# 3_adcs_circuits.net
KiCad netlist of a schematic drawn in Altium Designer
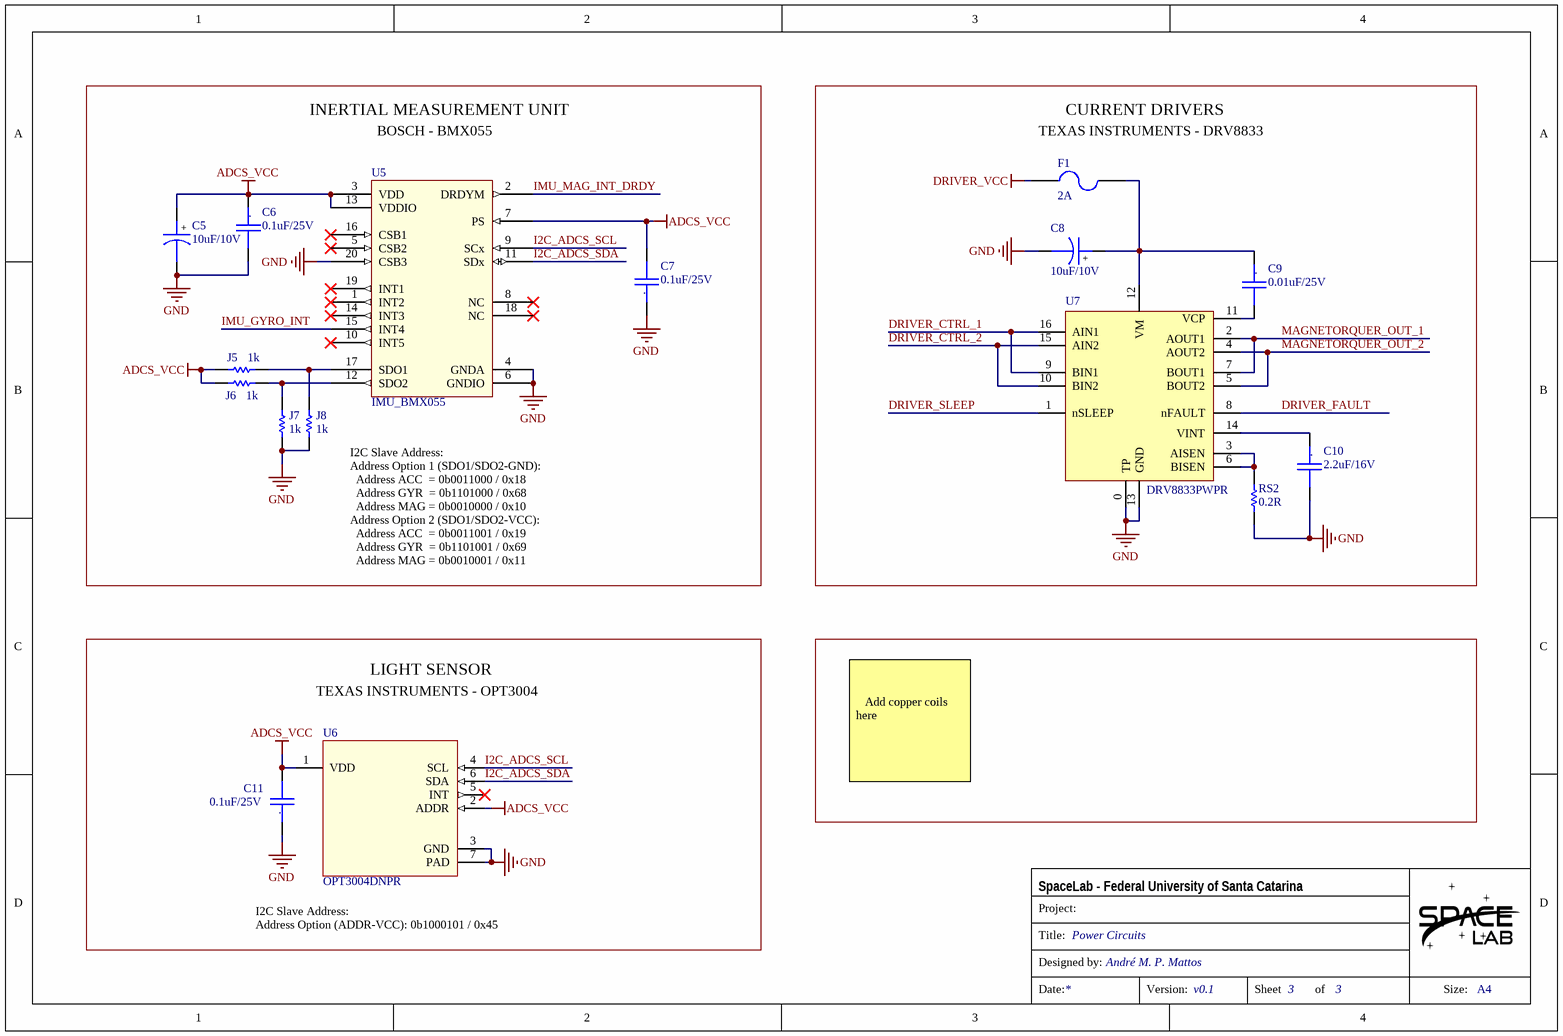
[diagram p0: 3_adcs_circuits.schdoc]

(export (version "E")
  (design (tool "Eeschema 10.0.6"))
  (components
    (comp (ref "C5")
      (value "10uF/10V")
      (footprint "CC0805_Tantalum")
      (description "CAP Tantalum 10uF 10V 20% 0805")
      (fields (field (name "PARTNUMBER") "TPSP106M010R2000"))
      (libsource (lib "schematics_library_legacy") (part "Cap_Tant_SMD_10uF_10V_0805"))
    )
    (comp (ref "C6")
      (value "0.1uF/25V")
      (footprint "CC0805")
      (description "CAP CER 0.1UF 25V 10% X7R 0805")
      (fields (field (name "PARTNUMBER") "CC0805KRX7R8BB104"))
      (libsource (lib "schematics_library_legacy") (part "Cap_Cer_X7R_0.1uF_25V_0805"))
    )
    (comp (ref "C7")
      (value "0.1uF/25V")
      (footprint "CC0805")
      (description "CAP CER 0.1UF 25V 10% X7R 0805")
      (fields (field (name "PARTNUMBER") "CC0805KRX7R8BB104"))
      (libsource (lib "schematics_library_legacy") (part "Cap_Cer_X7R_0.1uF_25V_0805"))
    )
    (comp (ref "C8")
      (value "10uF/10V")
      (footprint "CC0805_Tantalum")
      (description "CAP Tantalum 10uF 10V 20% 0805")
      (fields (field (name "PARTNUMBER") "TPSP106M010R2000"))
      (libsource (lib "schematics_library_legacy") (part "Cap_Tant_SMD_10uF_10V_0805"))
    )
    (comp (ref "C9")
      (value "0.01uF/25V")
      (footprint "CC0805")
      (description "CAP CER 0.01uF 25V 10% X7R 0805")
      (fields (field (name "PARTNUMBER") "CL21B103KAANNNC"))
      (libsource (lib "schematics_library_legacy") (part "Cap_Cer_X7R_0.01uF_50V_0805"))
    )
    (comp (ref "C10")
      (value "2.2uF/16V")
      (footprint "CC0805")
      (description "CAP CER 2.2uF 16V 10% X7R 0805")
      (fields (field (name "PARTNUMBER") "EMF212B7225KGHT"))
      (libsource (lib "schematics_library_legacy") (part "Cap_Cer_X7R_2.2uF_16V_0805"))
    )
    (comp (ref "C11")
      (value "0.1uF/25V")
      (footprint "CC0805")
      (description "CAP CER 0.1UF 25V 10% X7R 0805")
      (fields (field (name "PARTNUMBER") "CC0805KRX7R8BB104"))
      (libsource (lib "schematics_library_legacy") (part "Cap_Cer_X7R_0.1uF_25V_0805"))
    )
    (comp (ref "F1")
      (value "2A")
      (footprint "1206")
      (description "Surface Mount Fuses SMD 1206 Fast Action 2A")
      (fields (field (name "PARTNUMBER") "SF-1206FP200-2"))
      (libsource (lib "schematics_library_legacy") (part "Fuse"))
    )
    (comp (ref "J5")
      (value "1k")
      (footprint "0805")
      (description "RES 1.0K OHM 1/8W 1% 0805")
      (fields (field (name "PARTNUMBER") "RC0805FR-071KL"))
      (libsource (lib "schematics_library_legacy") (part "R1.0k_1%_1/8W_0805"))
    )
    (comp (ref "J6")
      (value "1k")
      (footprint "0805")
      (description "RES 1.0K OHM 1/8W 1% 0805")
      (fields (field (name "PARTNUMBER") "RC0805FR-071KL"))
      (libsource (lib "schematics_library_legacy") (part "R1.0k_1%_1/8W_0805"))
    )
    (comp (ref "J7")
      (value "1k")
      (footprint "0805")
      (description "RES 1.0K OHM 1/8W 1% 0805")
      (fields (field (name "PARTNUMBER") "RC0805FR-071KL"))
      (libsource (lib "schematics_library_legacy") (part "R1.0k_1%_1/8W_0805"))
    )
    (comp (ref "J8")
      (value "1k")
      (footprint "0805")
      (description "RES 1.0K OHM 1/8W 1% 0805")
      (fields (field (name "PARTNUMBER") "RC0805FR-071KL"))
      (libsource (lib "schematics_library_legacy") (part "R1.0k_1%_1/8W_0805"))
    )
    (comp (ref "RS2")
      (value "0.2R")
      (footprint "0805")
      (description "RES 0.2R OHM 1/4W 1% 0805")
      (fields (field (name "PARTNUMBER") "ERJ-U6SFR20V"))
      (libsource (lib "schematics_library_legacy") (part "R0.2_1%_1/4W_0805"))
    )
    (comp (ref "U5")
      (value "IMU_BMX055")
      (footprint "LGA20")
      (libsource (lib "schematics_library_legacy") (part "IMU_BMX055"))
    )
    (comp (ref "U6")
      (value "OPT3004DNPR")
      (footprint "DNP0006A")
      (description "No Description Available")
      (fields
        (field (name "MANUFACTURER") "Texas Instruments")
        (field (name "COPYRIGHT") "Copyright (C) 2018 Accelerated Designs. All rights reserved")
      )
      (libsource (lib "schematics_library_legacy") (part "OPT3004DNPR"))
    )
    (comp (ref "U7")
      (value "DRV8833PWPR")
      (footprint "16TTSSOP")
      (libsource (lib "schematics_library_legacy") (part "DRV8833PWPR"))
    )
  )
  (nets
    (net (code "1") (name "/DRIVER_CTRL_1") (class "Default")
      (node (ref "U7") (pin "16") (pinfunction "AIN1_16") (pintype "passive"))
      (node (ref "U7") (pin "9") (pinfunction "BIN1_9") (pintype "passive"))
    )
    (net (code "2") (name "/DRIVER_CTRL_2") (class "Default")
      (node (ref "U7") (pin "10") (pinfunction "BIN2_10") (pintype "passive"))
      (node (ref "U7") (pin "15") (pinfunction "AIN2_15") (pintype "passive"))
    )
    (net (code "3") (name "/DRIVER_FAULT") (class "Default")
      (node (ref "U7") (pin "8") (pinfunction "nFAULT_8") (pintype "passive"))
    )
    (net (code "4") (name "/DRIVER_SLEEP") (class "Default")
      (node (ref "U7") (pin "1") (pinfunction "nSLEEP_1") (pintype "passive"))
    )
    (net (code "5") (name "/I2C_ADCS_SCL") (class "Default")
      (node (ref "U5") (pin "9") (pinfunction "SCx_9") (pintype "input"))
      (node (ref "U6") (pin "4") (pinfunction "SCL_4") (pintype "input"))
    )
    (net (code "6") (name "/I2C_ADCS_SDA") (class "Default")
      (node (ref "U5") (pin "11") (pinfunction "SDx_11") (pintype "bidirectional"))
      (node (ref "U6") (pin "6") (pinfunction "SDA_6") (pintype "input"))
    )
    (net (code "7") (name "/IMU_GYRO_INT") (class "Default")
      (node (ref "U5") (pin "15") (pinfunction "INT4_15") (pintype "output"))
    )
    (net (code "8") (name "/IMU_MAG_INT_DRDY") (class "Default")
      (node (ref "U5") (pin "2") (pinfunction "DRDYM_2") (pintype "output"))
    )
    (net (code "9") (name "/MAGNETORQUER_OUT_1") (class "Default")
      (node (ref "U7") (pin "2") (pinfunction "AOUT1_2") (pintype "passive"))
      (node (ref "U7") (pin "7") (pinfunction "BOUT1_7") (pintype "passive"))
    )
    (net (code "10") (name "/MAGNETORQUER_OUT_2") (class "Default")
      (node (ref "U7") (pin "4") (pinfunction "AOUT2_4") (pintype "passive"))
      (node (ref "U7") (pin "5") (pinfunction "BOUT2_5") (pintype "passive"))
    )
    (net (code "11") (name "ADCS_VCC") (class "Default")
      (node (ref "C11") (pin "2") (pinfunction "2_2") (pintype "passive"))
      (node (ref "C5") (pin "1") (pinfunction "1_1") (pintype "passive"))
      (node (ref "C6") (pin "1") (pinfunction "1_1") (pintype "passive"))
      (node (ref "C7") (pin "2") (pinfunction "2_2") (pintype "passive"))
      (node (ref "J5") (pin "2") (pinfunction "2_2") (pintype "passive"))
      (node (ref "J6") (pin "2") (pinfunction "2_2") (pintype "passive"))
      (node (ref "U5") (pin "13") (pinfunction "VDDIO_13") (pintype "passive"))
      (node (ref "U5") (pin "3") (pinfunction "VDD_3") (pintype "passive"))
      (node (ref "U5") (pin "7") (pinfunction "PS_7") (pintype "input"))
      (node (ref "U6") (pin "1") (pinfunction "VDD_1") (pintype "power_in"))
      (node (ref "U6") (pin "2") (pinfunction "ADDR_2") (pintype "input"))
    )
    (net (code "12") (name "DRIVER_VCC") (class "Default")
      (node (ref "F1") (pin "2") (pinfunction "2_2") (pintype "passive"))
    )
    (net (code "13") (name "GND") (class "Default")
      (node (ref "C10") (pin "2") (pinfunction "2_2") (pintype "passive"))
      (node (ref "C11") (pin "1") (pinfunction "1_1") (pintype "passive"))
      (node (ref "C5") (pin "2") (pinfunction "2_2") (pintype "passive"))
      (node (ref "C6") (pin "2") (pinfunction "2_2") (pintype "passive"))
      (node (ref "C7") (pin "1") (pinfunction "1_1") (pintype "passive"))
      (node (ref "C8") (pin "2") (pinfunction "2_2") (pintype "passive"))
      (node (ref "J7") (pin "1") (pinfunction "1_1") (pintype "passive"))
      (node (ref "J8") (pin "1") (pinfunction "1_1") (pintype "passive"))
      (node (ref "RS2") (pin "1") (pinfunction "1_1") (pintype "passive"))
      (node (ref "U5") (pin "20") (pinfunction "CSB3_20") (pintype "input"))
      (node (ref "U5") (pin "4") (pinfunction "GNDA_4") (pintype "passive"))
      (node (ref "U5") (pin "6") (pinfunction "GNDIO_6") (pintype "passive"))
      (node (ref "U6") (pin "3") (pinfunction "GND_3") (pintype "power_in"))
      (node (ref "U6") (pin "7") (pinfunction "PAD_7") (pintype "passive"))
      (node (ref "U7") (pin "0") (pinfunction "TP_0") (pintype "passive"))
      (node (ref "U7") (pin "13") (pinfunction "GND_13") (pintype "passive"))
    )
    (net (code "14") (name "Net-(U5-SDO1)") (class "Default")
      (node (ref "J5") (pin "1") (pinfunction "1_1") (pintype "passive"))
      (node (ref "J8") (pin "2") (pinfunction "2_2") (pintype "passive"))
      (node (ref "U5") (pin "17") (pinfunction "SDO1_17") (pintype "passive"))
    )
    (net (code "15") (name "Net-(U5-SDO2)") (class "Default")
      (node (ref "J6") (pin "1") (pinfunction "1_1") (pintype "passive"))
      (node (ref "J7") (pin "2") (pinfunction "2_2") (pintype "passive"))
      (node (ref "U5") (pin "12") (pinfunction "SDO2_12") (pintype "output"))
    )
    (net (code "16") (name "Net-(U7-AISEN)") (class "Default")
      (node (ref "RS2") (pin "2") (pinfunction "2_2") (pintype "passive"))
      (node (ref "U7") (pin "3") (pinfunction "AISEN_3") (pintype "passive"))
      (node (ref "U7") (pin "6") (pinfunction "BISEN_6") (pintype "passive"))
    )
    (net (code "17") (name "Net-(U7-VCP)") (class "Default")
      (node (ref "C9") (pin "2") (pinfunction "2_2") (pintype "passive"))
      (node (ref "U7") (pin "11") (pinfunction "VCP_11") (pintype "passive"))
    )
    (net (code "18") (name "Net-(U7-VINT)") (class "Default")
      (node (ref "C10") (pin "1") (pinfunction "1_1") (pintype "passive"))
      (node (ref "U7") (pin "14") (pinfunction "VINT_14") (pintype "passive"))
    )
    (net (code "19") (name "Net-(U7-VM)") (class "Default")
      (node (ref "C8") (pin "1") (pinfunction "1_1") (pintype "passive"))
      (node (ref "C9") (pin "1") (pinfunction "1_1") (pintype "passive"))
      (node (ref "F1") (pin "1") (pinfunction "1_1") (pintype "passive"))
      (node (ref "U7") (pin "12") (pinfunction "VM_12") (pintype "passive"))
    )
    (net (code "20") (name "unconnected-(U5-CSB1-Pad16)") (class "Default")
      (node (ref "U5") (pin "16") (pinfunction "CSB1_16") (pintype "input+no_connect"))
    )
    (net (code "21") (name "unconnected-(U5-CSB2-Pad5)") (class "Default")
      (node (ref "U5") (pin "5") (pinfunction "CSB2_5") (pintype "input+no_connect"))
    )
    (net (code "22") (name "unconnected-(U5-INT1-Pad19)") (class "Default")
      (node (ref "U5") (pin "19") (pinfunction "INT1_19") (pintype "output+no_connect"))
    )
    (net (code "23") (name "unconnected-(U5-INT2-Pad1)") (class "Default")
      (node (ref "U5") (pin "1") (pinfunction "INT2_1") (pintype "output+no_connect"))
    )
    (net (code "24") (name "unconnected-(U5-INT3-Pad14)") (class "Default")
      (node (ref "U5") (pin "14") (pinfunction "INT3_14") (pintype "output+no_connect"))
    )
    (net (code "25") (name "unconnected-(U5-INT5-Pad10)") (class "Default")
      (node (ref "U5") (pin "10") (pinfunction "INT5_10") (pintype "output+no_connect"))
    )
    (net (code "26") (name "unconnected-(U5-NC-Pad8)") (class "Default")
      (node (ref "U5") (pin "8") (pinfunction "NC_8") (pintype "passive+no_connect"))
    )
    (net (code "27") (name "unconnected-(U5-NC-Pad18)") (class "Default")
      (node (ref "U5") (pin "18") (pinfunction "NC_18") (pintype "passive+no_connect"))
    )
    (net (code "28") (name "unconnected-(U6-INT-Pad5)") (class "Default")
      (node (ref "U6") (pin "5") (pinfunction "INT_5") (pintype "output+no_connect"))
    )
  )
)
